# HS1-HS2.net
KiCad netlist of a schematic drawn in Altium Designer
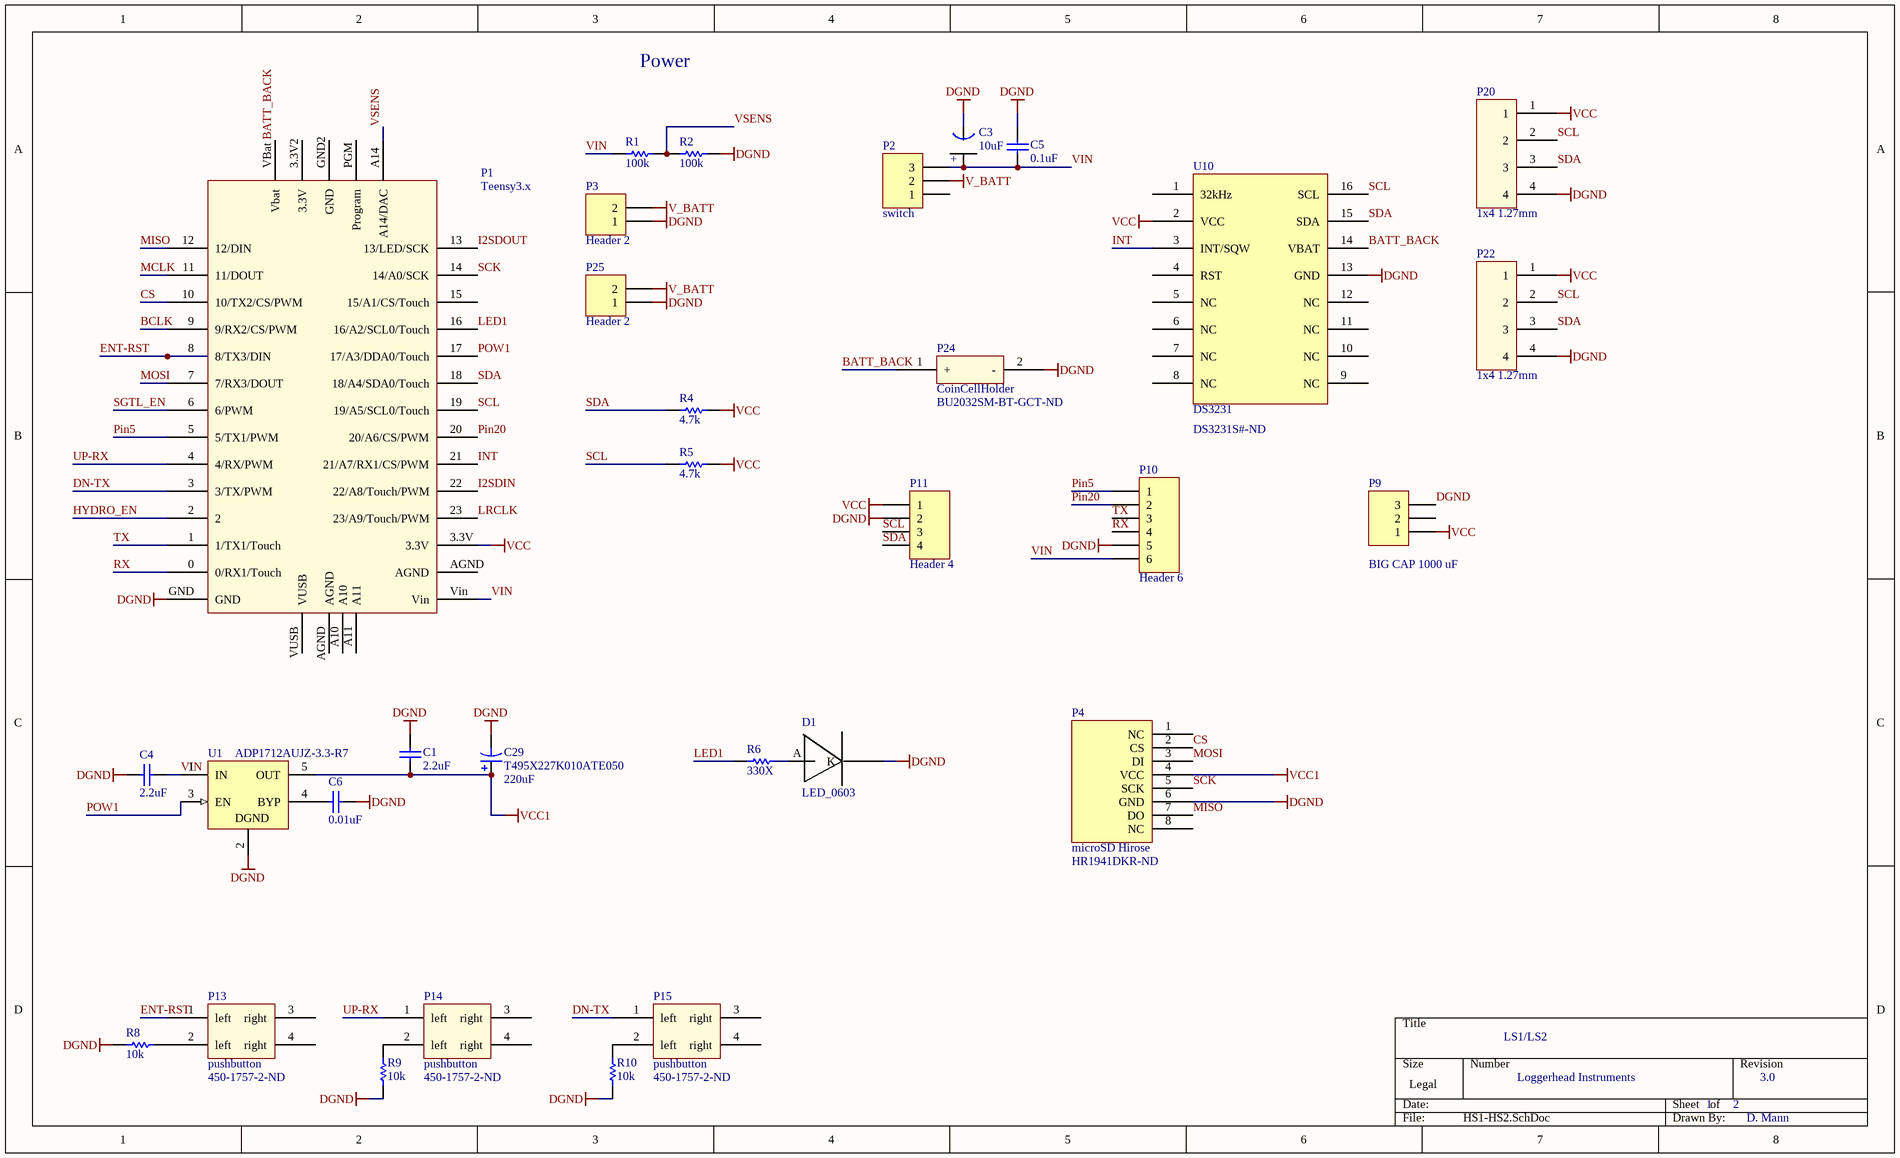
[diagram p0: HS1-HS2.SchDoc]

(export (version "E")
  (design (tool "Eeschema 10.0.6"))
  (components
    (comp (ref "C1")
      (value "2.2uF")
      (footprint "0402")
      (description "Ceramic Chip Capacitor - Standard")
      (fields (field (name "PUBLISHER") "Altium Limited"))
      (libsource (lib "KEMET Chip Capacitor") (part "C0402"))
    )
    (comp (ref "C3") (value "10uF") (footprint "Tant0805") (libsource (lib "Loggerhead") (part "Tant0805")))
    (comp (ref "C4")
      (value "2.2uF")
      (footprint "0402")
      (description "Ceramic Chip Capacitor - Standard")
      (fields (field (name "PUBLISHER") "Altium Limited"))
      (libsource (lib "KEMET Chip Capacitor") (part "C0402"))
    )
    (comp (ref "C5")
      (value "0.1uF")
      (footprint "0402")
      (description "Ceramic Chip Capacitor - Standard")
      (fields (field (name "PUBLISHER") "Altium Limited"))
      (libsource (lib "KEMET Chip Capacitor") (part "C0402"))
    )
    (comp (ref "C6")
      (value "0.01uF")
      (footprint "0402")
      (description "Ceramic Chip Capacitor - Standard")
      (fields (field (name "PUBLISHER") "Altium Limited"))
      (libsource (lib "KEMET Chip Capacitor") (part "C0402"))
    )
    (comp (ref "C29")
      (value "T495X227K010ATE050")
      (footprint "X")
      (description "Solid Tantalum Chip Capacitor, Standard T495 Series - Low ESR, Surge Robust")
      (fields (field (name "ALTIUM_VALUE") "220uF") (field (name "PUBLISHER") "Altium Limited"))
      (libsource (lib "KEMET Chip Capacitor") (part "T495X"))
    )
    (comp (ref "D1")
      (value "LED_0603")
      (footprint "Diode0603")
      (libsource (lib "Loggerhead") (part "LED_0603"))
    )
    (comp (ref "P1")
      (value "Teensy3.x")
      (footprint "Teensy3.x")
      (libsource (lib "Teensy") (part "Teensy3.x"))
    )
    (comp (ref "P2")
      (value "switch")
      (footprint "HDR1X3")
      (description "Header, 3-Pin")
      (fields (field (name "PUBLISHER") "Altium Limited"))
      (libsource (lib "Miscellaneous Connectors") (part "Header 3"))
    )
    (comp (ref "P3")
      (value "Header 2")
      (footprint "HDR1X2")
      (description "Header, 2-Pin")
      (fields (field (name "PUBLISHER") "Altium Limited"))
      (libsource (lib "Miscellaneous Connectors") (part "Header 2"))
    )
    (comp (ref "P4")
      (value "microSD Hirose")
      (footprint "DM3D microSD")
      (fields (field (name "SUPPLIER PART NUMBER 1") "HR1941DKR-ND"))
      (libsource (lib "Loggerhead") (part "microSD Hirose"))
    )
    (comp (ref "P9")
      (value "BIG CAP 1000 uF")
      (footprint "HDR1X3")
      (description "Header, 3-Pin")
      (fields (field (name "PUBLISHER") "Altium Limited"))
      (libsource (lib "Miscellaneous Connectors") (part "Header 3"))
    )
    (comp (ref "P10")
      (value "Header 6")
      (footprint "HDR1X6")
      (description "Header, 6-Pin")
      (fields (field (name "PUBLISHER") "Altium Limited"))
      (libsource (lib "Miscellaneous Connectors") (part "Header 6"))
    )
    (comp (ref "P11")
      (value "Header 4")
      (footprint "HDR1X4")
      (description "Header, 4-Pin")
      (fields (field (name "PUBLISHER") "Altium Limited"))
      (libsource (lib "Miscellaneous Connectors") (part "Header 4"))
    )
    (comp (ref "P13")
      (value "pushbutton")
      (footprint "SOP4")
      (fields (field (name "SUPPLIER PART NUMBER 1") "450-1757-2-ND"))
      (libsource (lib "Loggerhead") (part "pushbutton"))
    )
    (comp (ref "P14")
      (value "pushbutton")
      (footprint "SOP4")
      (fields (field (name "SUPPLIER PART NUMBER 1") "450-1757-2-ND"))
      (libsource (lib "Loggerhead") (part "pushbutton"))
    )
    (comp (ref "P15")
      (value "pushbutton")
      (footprint "SOP4")
      (fields (field (name "SUPPLIER PART NUMBER 1") "450-1757-2-ND"))
      (libsource (lib "Loggerhead") (part "pushbutton"))
    )
    (comp (ref "P20")
      (value "1x4 1.27mm")
      (footprint "Header1x4 1.27mm")
      (libsource (lib "Loggerhead") (part "Header 1x4 1.27mm"))
    )
    (comp (ref "P22")
      (value "1x4 1.27mm")
      (footprint "Header1x4 1.27mm")
      (libsource (lib "Loggerhead") (part "Header 1x4 1.27mm"))
    )
    (comp (ref "P24")
      (value "CoinCellHolder")
      (footprint "CoinCellHolder")
      (fields (field (name "SUPPLIER PART NUMBER 1") "BU2032SM-BT-GCT-ND"))
      (libsource (lib "Loggerhead") (part "CoinCellHolder"))
    )
    (comp (ref "P25")
      (value "Header 2")
      (footprint "HDR1X2")
      (description "Header, 2-Pin")
      (fields (field (name "PUBLISHER") "Altium Limited"))
      (libsource (lib "Miscellaneous Connectors") (part "Header 2"))
    )
    (comp (ref "R1")
      (value "100k")
      (footprint "3-0603")
      (fields (field (name "PUBLISHER") "Altium Limited"))
      (libsource (lib "Panasonic Resistor") (part "ERJ3RK"))
    )
    (comp (ref "R2")
      (value "100k")
      (footprint "3-0603")
      (fields (field (name "PUBLISHER") "Altium Limited"))
      (libsource (lib "Panasonic Resistor") (part "ERJ3RK"))
    )
    (comp (ref "R4")
      (value "4.7k")
      (footprint "3-0603")
      (fields (field (name "PUBLISHER") "Altium Limited"))
      (libsource (lib "Panasonic Resistor") (part "ERJ3RK"))
    )
    (comp (ref "R5")
      (value "4.7k")
      (footprint "3-0603")
      (fields (field (name "PUBLISHER") "Altium Limited"))
      (libsource (lib "Panasonic Resistor") (part "ERJ3RK"))
    )
    (comp (ref "R6")
      (value "330X")
      (footprint "3-0603")
      (fields (field (name "PUBLISHER") "Altium Limited"))
      (libsource (lib "Panasonic Resistor") (part "ERJ3RK"))
    )
    (comp (ref "R8")
      (value "10k")
      (footprint "3-0603")
      (fields (field (name "PUBLISHER") "Altium Limited"))
      (libsource (lib "Panasonic Resistor") (part "ERJ3RK"))
    )
    (comp (ref "R9")
      (value "10k")
      (footprint "3-0603")
      (fields (field (name "PUBLISHER") "Altium Limited"))
      (libsource (lib "Panasonic Resistor") (part "ERJ3RK"))
    )
    (comp (ref "R10")
      (value "10k")
      (footprint "3-0603")
      (fields (field (name "PUBLISHER") "Altium Limited"))
      (libsource (lib "Panasonic Resistor") (part "ERJ3RK"))
    )
    (comp (ref "U1")
      (value "ADP1712AUJZ-3.3-R7")
      (footprint "MF05A_N")
      (description "Micropower, 150mA Low-Noise Ultra Low-Dropout CMOS Voltage Regulator")
      (fields
        (field (name "PARTNUMBER") "LP3985IM5-3.3")
        (field (name "MANUFACTURER") "National Semiconductor")
        (field (name "PUBLISHER") "Altium Limited")
      )
      (libsource (lib "NSC LDO") (part "LP3985IM5-3.3"))
    )
    (comp (ref "U10")
      (value "DS3231")
      (footprint "DS3231")
      (fields (field (name "SUPPLIER PART NUMBER 1") "DS3231S#-ND"))
      (libsource (lib "Loggerhead") (part "DS3231"))
    )
  )
  (nets
    (net (code "1") (name "/BATT_BACK") (class "Default")
      (node (ref "P1") (pin "VBat") (pinfunction "Vbat_VBat") (pintype "passive"))
      (node (ref "P24") (pin "1") (pinfunction "+_1") (pintype "passive"))
      (node (ref "U10") (pin "14") (pinfunction "VBAT_14") (pintype "power_in"))
    )
    (net (code "2") (name "/BCLK") (class "Default")
      (node (ref "P1") (pin "9") (pinfunction "9/RX2/CS/PWM_9") (pintype "passive"))
    )
    (net (code "3") (name "/CS") (class "Default")
      (node (ref "P1") (pin "10") (pinfunction "10/TX2/CS/PWM_10") (pintype "passive"))
      (node (ref "P4") (pin "2") (pinfunction "CS_2") (pintype "passive"))
    )
    (net (code "4") (name "/DN-TX") (class "Default")
      (node (ref "P1") (pin "3") (pinfunction "3/TX/PWM_3") (pintype "passive"))
      (node (ref "P15") (pin "1") (pinfunction "left_1") (pintype "passive"))
    )
    (net (code "5") (name "/ENT-RST") (class "Default")
      (node (ref "P1") (pin "8") (pinfunction "8/TX3/DIN_8") (pintype "passive"))
      (node (ref "P13") (pin "1") (pinfunction "left_1") (pintype "passive"))
    )
    (net (code "6") (name "/HYDRO_EN") (class "Default")
      (node (ref "P1") (pin "2") (pinfunction "2_2") (pintype "passive"))
    )
    (net (code "7") (name "/I2SDIN") (class "Default")
      (node (ref "P1") (pin "22") (pinfunction "22/A8/Touch/PWM_22") (pintype "passive"))
    )
    (net (code "8") (name "/I2SDOUT") (class "Default")
      (node (ref "P1") (pin "13") (pinfunction "13/LED/SCK_13") (pintype "passive"))
    )
    (net (code "9") (name "/INT") (class "Default")
      (node (ref "P1") (pin "21") (pinfunction "21/A7/RX1/CS/PWM_21") (pintype "passive"))
      (node (ref "U10") (pin "3") (pinfunction "INT/SQW_3") (pintype "passive"))
    )
    (net (code "10") (name "/LED1") (class "Default")
      (node (ref "P1") (pin "16") (pinfunction "16/A2/SCL0/Touch_16") (pintype "passive"))
      (node (ref "R6") (pin "1") (pinfunction "1_1") (pintype "passive"))
    )
    (net (code "11") (name "/LRCLK") (class "Default")
      (node (ref "P1") (pin "23") (pinfunction "23/A9/Touch/PWM_23") (pintype "passive"))
    )
    (net (code "12") (name "/MCLK") (class "Default")
      (node (ref "P1") (pin "11") (pinfunction "11/DOUT_11") (pintype "passive"))
    )
    (net (code "13") (name "/MISO") (class "Default")
      (node (ref "P1") (pin "12") (pinfunction "12/DIN_12") (pintype "passive"))
      (node (ref "P4") (pin "7") (pinfunction "DO_7") (pintype "passive"))
    )
    (net (code "14") (name "/MOSI") (class "Default")
      (node (ref "P1") (pin "7") (pinfunction "7/RX3/DOUT_7") (pintype "passive"))
      (node (ref "P4") (pin "3") (pinfunction "DI_3") (pintype "passive"))
    )
    (net (code "15") (name "/POW1") (class "Default")
      (node (ref "P1") (pin "17") (pinfunction "17/A3/DDA0/Touch_17") (pintype "passive"))
      (node (ref "U1") (pin "3") (pinfunction "EN_3") (pintype "input"))
    )
    (net (code "16") (name "/Pin5") (class "Default")
      (node (ref "P1") (pin "5") (pinfunction "5/TX1/PWM_5") (pintype "passive"))
      (node (ref "P10") (pin "1") (pinfunction "1_1") (pintype "passive"))
    )
    (net (code "17") (name "/Pin20") (class "Default")
      (node (ref "P1") (pin "20") (pinfunction "20/A6/CS/PWM_20") (pintype "passive"))
      (node (ref "P10") (pin "2") (pinfunction "2_2") (pintype "passive"))
    )
    (net (code "18") (name "/RX") (class "Default")
      (node (ref "P1") (pin "0") (pinfunction "0/RX1/Touch_0") (pintype "passive"))
      (node (ref "P10") (pin "4") (pinfunction "4_4") (pintype "passive"))
    )
    (net (code "19") (name "/SCK") (class "Default")
      (node (ref "P1") (pin "14") (pinfunction "14/A0/SCK_14") (pintype "passive"))
      (node (ref "P4") (pin "5") (pinfunction "SCK_5") (pintype "passive"))
    )
    (net (code "20") (name "/SCL") (class "Default")
      (node (ref "P1") (pin "19") (pinfunction "19/A5/SCL0/Touch_19") (pintype "passive"))
      (node (ref "P11") (pin "3") (pinfunction "3_3") (pintype "passive"))
      (node (ref "P20") (pin "2") (pinfunction "2_2") (pintype "passive"))
      (node (ref "P22") (pin "2") (pinfunction "2_2") (pintype "passive"))
      (node (ref "R5") (pin "1") (pinfunction "1_1") (pintype "passive"))
      (node (ref "U10") (pin "16") (pinfunction "SCL_16") (pintype "passive"))
    )
    (net (code "21") (name "/SDA") (class "Default")
      (node (ref "P1") (pin "18") (pinfunction "18/A4/SDA0/Touch_18") (pintype "passive"))
      (node (ref "P11") (pin "4") (pinfunction "4_4") (pintype "passive"))
      (node (ref "P20") (pin "3") (pinfunction "3_3") (pintype "passive"))
      (node (ref "P22") (pin "3") (pinfunction "3_3") (pintype "passive"))
      (node (ref "R4") (pin "1") (pinfunction "1_1") (pintype "passive"))
      (node (ref "U10") (pin "15") (pinfunction "SDA_15") (pintype "passive"))
    )
    (net (code "22") (name "/SGTL_EN") (class "Default")
      (node (ref "P1") (pin "6") (pinfunction "6/PWM_6") (pintype "passive"))
    )
    (net (code "23") (name "/TX") (class "Default")
      (node (ref "P1") (pin "1") (pinfunction "1/TX1/Touch_1") (pintype "passive"))
      (node (ref "P10") (pin "3") (pinfunction "3_3") (pintype "passive"))
    )
    (net (code "24") (name "/UP-RX") (class "Default")
      (node (ref "P1") (pin "4") (pinfunction "4/RX/PWM_4") (pintype "passive"))
      (node (ref "P14") (pin "1") (pinfunction "left_1") (pintype "passive"))
    )
    (net (code "25") (name "/VIN") (class "Default")
      (node (ref "C3") (pin "2") (pinfunction "+_2") (pintype "passive"))
      (node (ref "C4") (pin "1") (pinfunction "1_1") (pintype "passive"))
      (node (ref "C5") (pin "1") (pinfunction "1_1") (pintype "passive"))
      (node (ref "P1") (pin "Vin") (pinfunction "Vin_Vin") (pintype "passive"))
      (node (ref "P10") (pin "6") (pinfunction "6_6") (pintype "passive"))
      (node (ref "P2") (pin "3") (pinfunction "3_3") (pintype "passive"))
      (node (ref "R1") (pin "2") (pinfunction "2_2") (pintype "passive"))
      (node (ref "U1") (pin "1") (pinfunction "IN_1") (pintype "power_in"))
    )
    (net (code "26") (name "/VSENS") (class "Default")
      (node (ref "P1") (pin "A14") (pinfunction "A14/DAC_A14") (pintype "passive"))
      (node (ref "R1") (pin "1") (pinfunction "1_1") (pintype "passive"))
      (node (ref "R2") (pin "2") (pinfunction "2_2") (pintype "passive"))
    )
    (net (code "27") (name "DGND") (class "Default")
      (node (ref "C1") (pin "1") (pinfunction "1_1") (pintype "passive"))
      (node (ref "C29") (pin "2") (pinfunction "2_2") (pintype "passive"))
      (node (ref "C3") (pin "1") (pinfunction "GND_1") (pintype "passive"))
      (node (ref "C4") (pin "2") (pinfunction "2_2") (pintype "passive"))
      (node (ref "C5") (pin "2") (pinfunction "2_2") (pintype "passive"))
      (node (ref "C6") (pin "2") (pinfunction "2_2") (pintype "passive"))
      (node (ref "D1") (pin "K") (pinfunction "K_K") (pintype "passive"))
      (node (ref "P1") (pin "GND") (pinfunction "GND_GND") (pintype "passive"))
      (node (ref "P10") (pin "5") (pinfunction "5_5") (pintype "passive"))
      (node (ref "P11") (pin "2") (pinfunction "2_2") (pintype "passive"))
      (node (ref "P20") (pin "4") (pinfunction "4_4") (pintype "passive"))
      (node (ref "P22") (pin "4") (pinfunction "4_4") (pintype "passive"))
      (node (ref "P24") (pin "2") (pinfunction "-_2") (pintype "passive"))
      (node (ref "P25") (pin "1") (pinfunction "1_1") (pintype "passive"))
      (node (ref "P3") (pin "1") (pinfunction "1_1") (pintype "passive"))
      (node (ref "P4") (pin "6") (pinfunction "GND_6") (pintype "passive"))
      (node (ref "P9") (pin "3") (pinfunction "3_3") (pintype "passive"))
      (node (ref "R10") (pin "2") (pinfunction "2_2") (pintype "passive"))
      (node (ref "R2") (pin "1") (pinfunction "1_1") (pintype "passive"))
      (node (ref "R8") (pin "2") (pinfunction "2_2") (pintype "passive"))
      (node (ref "R9") (pin "2") (pinfunction "2_2") (pintype "passive"))
      (node (ref "U1") (pin "2") (pinfunction "GND_2") (pintype "power_in"))
      (node (ref "U10") (pin "13") (pinfunction "GND_13") (pintype "passive"))
    )
    (net (code "28") (name "Net-(D1-PadA)") (class "Default")
      (node (ref "D1") (pin "A") (pinfunction "A_A") (pintype "passive"))
      (node (ref "R6") (pin "2") (pinfunction "2_2") (pintype "passive"))
    )
    (net (code "29") (name "Net-(P13-left-Pad2)") (class "Default")
      (node (ref "P13") (pin "2") (pinfunction "left_2") (pintype "passive"))
      (node (ref "R8") (pin "1") (pinfunction "1_1") (pintype "passive"))
    )
    (net (code "30") (name "Net-(P14-left-Pad2)") (class "Default")
      (node (ref "P14") (pin "2") (pinfunction "left_2") (pintype "passive"))
      (node (ref "R9") (pin "1") (pinfunction "1_1") (pintype "passive"))
    )
    (net (code "31") (name "Net-(P15-left-Pad2)") (class "Default")
      (node (ref "P15") (pin "2") (pinfunction "left_2") (pintype "passive"))
      (node (ref "R10") (pin "1") (pinfunction "1_1") (pintype "passive"))
    )
    (net (code "32") (name "Net-(U1-BYP)") (class "Default")
      (node (ref "C6") (pin "1") (pinfunction "1_1") (pintype "passive"))
      (node (ref "U1") (pin "4") (pinfunction "BYP_4") (pintype "passive"))
    )
    (net (code "33") (name "VCC") (class "Default")
      (node (ref "P1") (pin "3.3V") (pinfunction "3.3V_3.3V") (pintype "passive"))
      (node (ref "P11") (pin "1") (pinfunction "1_1") (pintype "passive"))
      (node (ref "P20") (pin "1") (pinfunction "1_1") (pintype "passive"))
      (node (ref "P22") (pin "1") (pinfunction "1_1") (pintype "passive"))
      (node (ref "P9") (pin "1") (pinfunction "1_1") (pintype "passive"))
      (node (ref "R4") (pin "2") (pinfunction "2_2") (pintype "passive"))
      (node (ref "R5") (pin "2") (pinfunction "2_2") (pintype "passive"))
      (node (ref "U10") (pin "2") (pinfunction "VCC_2") (pintype "power_in"))
    )
    (net (code "34") (name "VCC1") (class "Default")
      (node (ref "C1") (pin "2") (pinfunction "2_2") (pintype "passive"))
      (node (ref "C29") (pin "1") (pinfunction "1_1") (pintype "passive"))
      (node (ref "P4") (pin "4") (pinfunction "VCC_4") (pintype "passive"))
      (node (ref "U1") (pin "5") (pinfunction "OUT_5") (pintype "power_in"))
    )
    (net (code "35") (name "V_BATT") (class "Default")
      (node (ref "P2") (pin "2") (pinfunction "2_2") (pintype "passive"))
      (node (ref "P25") (pin "2") (pinfunction "2_2") (pintype "passive"))
      (node (ref "P3") (pin "2") (pinfunction "2_2") (pintype "passive"))
    )
    (net (code "36") (name "unconnected-(P1-3.3V-Pad3.3V2)") (class "Default")
      (node (ref "P1") (pin "3.3V2") (pinfunction "3.3V_3.3V2") (pintype "passive"))
    )
    (net (code "37") (name "unconnected-(P1-15{slash}A1{slash}CS{slash}Touch-Pad15)") (class "Default")
      (node (ref "P1") (pin "15") (pinfunction "15/A1/CS/Touch_15") (pintype "passive"))
    )
    (net (code "38") (name "unconnected-(P1-GND-PadGND2)") (class "Default")
      (node (ref "P1") (pin "GND2") (pinfunction "GND_GND2") (pintype "passive"))
    )
    (net (code "39") (name "unconnected-(P1-PadA10)") (class "Default")
      (node (ref "P1") (pin "A10") (pinfunction "A10_A10") (pintype "passive"))
    )
    (net (code "40") (name "unconnected-(P1-PadA11)") (class "Default")
      (node (ref "P1") (pin "A11") (pinfunction "A11_A11") (pintype "passive"))
    )
    (net (code "41") (name "unconnected-(P1-PadAGND)") (class "Default")
      (node (ref "P1") (pin "AGND") (pinfunction "AGND_AGND") (pintype "passive"))
    )
    (net (code "42") (name "unconnected-(P1-PadAGND)_1") (class "Default")
      (node (ref "P1") (pin "AGND") (pinfunction "AGND_AGND") (pintype "passive"))
    )
    (net (code "43") (name "unconnected-(P1-PadVUSB)") (class "Default")
      (node (ref "P1") (pin "VUSB") (pinfunction "VUSB_VUSB") (pintype "passive"))
    )
    (net (code "44") (name "unconnected-(P1-Program-PadPGM)") (class "Default")
      (node (ref "P1") (pin "PGM") (pinfunction "Program_PGM") (pintype "passive"))
    )
    (net (code "45") (name "unconnected-(P2-Pad1)") (class "Default")
      (node (ref "P2") (pin "1") (pinfunction "1_1") (pintype "passive"))
    )
    (net (code "46") (name "unconnected-(P4-NC-Pad1)") (class "Default")
      (node (ref "P4") (pin "1") (pinfunction "NC_1") (pintype "passive"))
    )
    (net (code "47") (name "unconnected-(P4-NC-Pad8)") (class "Default")
      (node (ref "P4") (pin "8") (pinfunction "NC_8") (pintype "passive"))
    )
    (net (code "48") (name "unconnected-(P9-Pad2)") (class "Default")
      (node (ref "P9") (pin "2") (pinfunction "2_2") (pintype "passive"))
    )
    (net (code "49") (name "unconnected-(P13-right-Pad3)") (class "Default")
      (node (ref "P13") (pin "3") (pinfunction "right_3") (pintype "passive"))
    )
    (net (code "50") (name "unconnected-(P13-right-Pad4)") (class "Default")
      (node (ref "P13") (pin "4") (pinfunction "right_4") (pintype "passive"))
    )
    (net (code "51") (name "unconnected-(P14-right-Pad3)") (class "Default")
      (node (ref "P14") (pin "3") (pinfunction "right_3") (pintype "passive"))
    )
    (net (code "52") (name "unconnected-(P14-right-Pad4)") (class "Default")
      (node (ref "P14") (pin "4") (pinfunction "right_4") (pintype "passive"))
    )
    (net (code "53") (name "unconnected-(P15-right-Pad3)") (class "Default")
      (node (ref "P15") (pin "3") (pinfunction "right_3") (pintype "passive"))
    )
    (net (code "54") (name "unconnected-(P15-right-Pad4)") (class "Default")
      (node (ref "P15") (pin "4") (pinfunction "right_4") (pintype "passive"))
    )
    (net (code "55") (name "unconnected-(U10-32kHz-Pad1)") (class "Default")
      (node (ref "U10") (pin "1") (pinfunction "32kHz_1") (pintype "passive"))
    )
    (net (code "56") (name "unconnected-(U10-NC-Pad5)") (class "Default")
      (node (ref "U10") (pin "5") (pinfunction "NC_5") (pintype "passive"))
    )
    (net (code "57") (name "unconnected-(U10-NC-Pad6)") (class "Default")
      (node (ref "U10") (pin "6") (pinfunction "NC_6") (pintype "passive"))
    )
    (net (code "58") (name "unconnected-(U10-NC-Pad7)") (class "Default")
      (node (ref "U10") (pin "7") (pinfunction "NC_7") (pintype "passive"))
    )
    (net (code "59") (name "unconnected-(U10-NC-Pad8)") (class "Default")
      (node (ref "U10") (pin "8") (pinfunction "NC_8") (pintype "passive"))
    )
    (net (code "60") (name "unconnected-(U10-NC-Pad9)") (class "Default")
      (node (ref "U10") (pin "9") (pinfunction "NC_9") (pintype "passive"))
    )
    (net (code "61") (name "unconnected-(U10-NC-Pad10)") (class "Default")
      (node (ref "U10") (pin "10") (pinfunction "NC_10") (pintype "passive"))
    )
    (net (code "62") (name "unconnected-(U10-NC-Pad11)") (class "Default")
      (node (ref "U10") (pin "11") (pinfunction "NC_11") (pintype "passive"))
    )
    (net (code "63") (name "unconnected-(U10-NC-Pad12)") (class "Default")
      (node (ref "U10") (pin "12") (pinfunction "NC_12") (pintype "passive"))
    )
    (net (code "64") (name "unconnected-(U10-RST-Pad4)") (class "Default")
      (node (ref "U10") (pin "4") (pinfunction "RST_4") (pintype "passive"))
    )
  )
)
